# Battery_Module_Dev_Contacts.net
KiCad netlist of a schematic drawn in Altium Designer
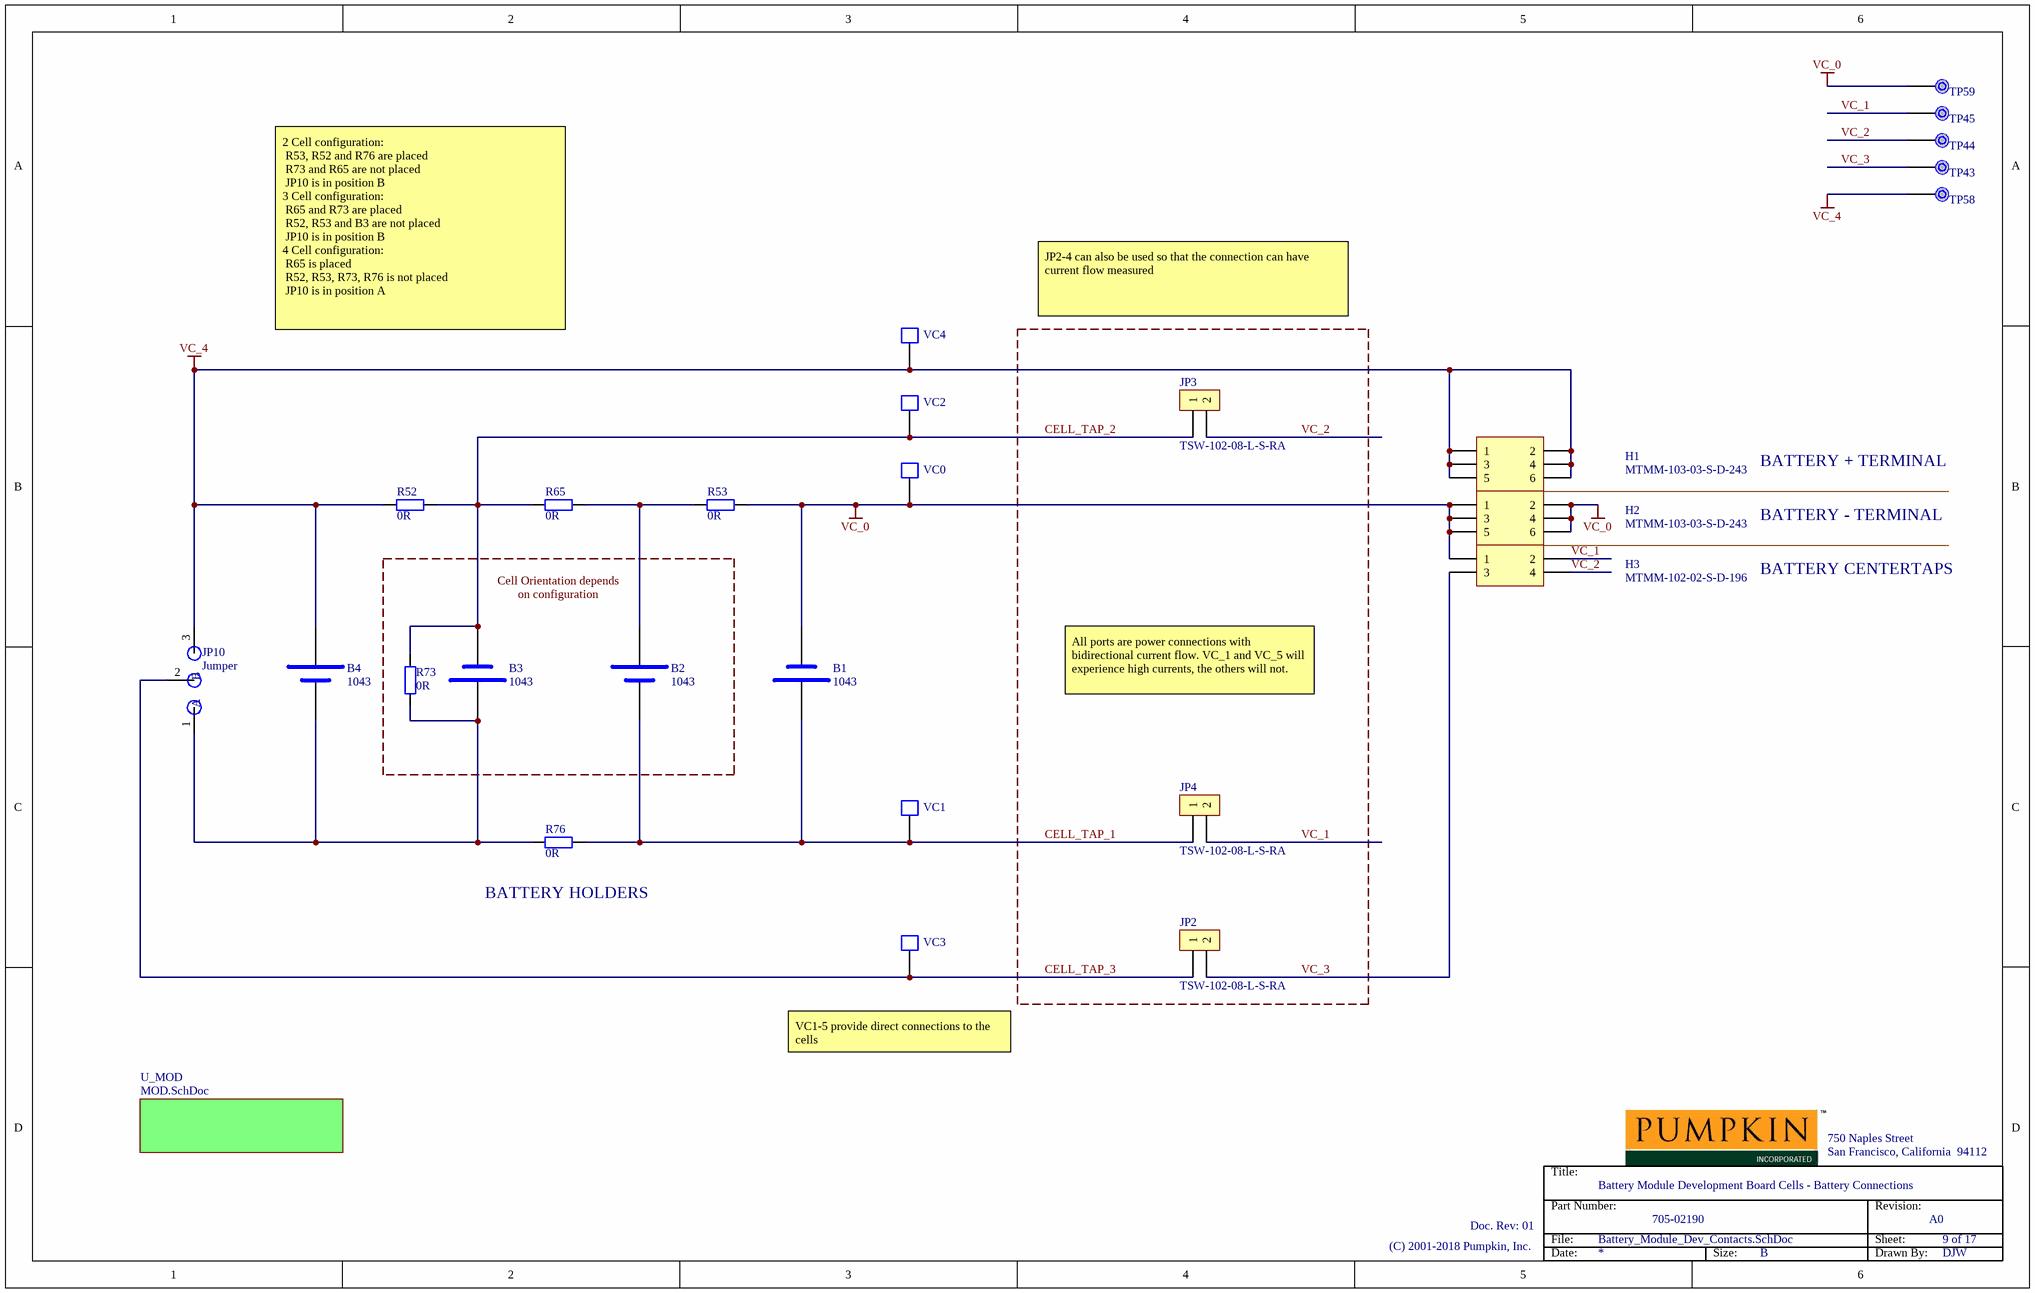
[diagram p0: Battery_Module_Dev_Contacts.SchDoc]

(export (version "E")
  (design (tool "Eeschema 10.0.6"))
  (components
    (comp (ref "B1")
      (value "1043")
      (footprint "1043")
      (description "Battery 18650 Holder")
      (libsource (lib "Supernova Connectors") (part "1043"))
    )
    (comp (ref "B2")
      (value "1043")
      (footprint "1043 - non-polar")
      (description "Battery 18650 Holder")
      (libsource (lib "Supernova Connectors") (part "1043"))
    )
    (comp (ref "B3")
      (value "1043")
      (footprint "1043 - non-polar")
      (description "Battery 18650 Holder")
      (libsource (lib "Supernova Connectors") (part "1043"))
    )
    (comp (ref "B4")
      (value "1043")
      (footprint "1043")
      (description "Battery 18650 Holder")
      (libsource (lib "Supernova Connectors") (part "1043"))
    )
    (comp (ref "H1")
      (value "MTMM-103-03-S-D-243")
      (footprint "MTMM-103-03-S-D-243")
      (description "Header 3x2 TH thru-board 2mm")
      (libsource (lib "Supernova Connectors") (part "MTMM-103-03-S-D-243"))
    )
    (comp (ref "H2")
      (value "MTMM-103-03-S-D-243")
      (footprint "MTMM-103-03-S-D-243")
      (description "Header 3x2 TH thru-board 2mm")
      (libsource (lib "Supernova Connectors") (part "MTMM-103-03-S-D-243"))
    )
    (comp (ref "H3")
      (value "MTMM-102-02-S-D-196")
      (footprint "MTMM-102-02-S-D-196")
      (description "Header 2x2 TH thru-board 2mm")
      (libsource (lib "Supernova Connectors") (part "MTMM-102-02-S-D-196"))
    )
    (comp (ref "JP2")
      (value "TSW-102-08-L-S-RA")
      (footprint "HDR1X2HTH")
      (description "Header 2x1 RA TH")
      (libsource (lib "Supernova Connectors") (part "TSW-102-08-L-S-RA"))
    )
    (comp (ref "JP3")
      (value "TSW-102-08-L-S-RA")
      (footprint "HDR1X2HTH")
      (description "Header 2x1 RA TH")
      (libsource (lib "Supernova Connectors") (part "TSW-102-08-L-S-RA"))
    )
    (comp (ref "JP4")
      (value "TSW-102-08-L-S-RA")
      (footprint "HDR1X2HTH")
      (description "Header 2x1 RA TH")
      (libsource (lib "Supernova Connectors") (part "TSW-102-08-L-S-RA"))
    )
    (comp (ref "JP10")
      (value "Jumper")
      (footprint "0805 RES 2 way jumper")
      (description "Jumper 0805 2 pos")
      (libsource (lib "Supernova Resistors") (part "Jumper 2 way 0805"))
    )
    (comp (ref "R52")
      (value "0R")
      (footprint "2512 RES")
      (description "Resistor 0R 2512 1W")
      (libsource (lib "") (part "Resistor 0R 2512_2"))
    )
    (comp (ref "R53")
      (value "0R")
      (footprint "2512 RES")
      (description "Resistor 0R 2512 1W")
      (libsource (lib "") (part "Resistor 0R 2512_1"))
    )
    (comp (ref "R65")
      (value "0R")
      (footprint "2512 RES")
      (description "Resistor 0R 2512 1W")
      (libsource (lib "") (part "Resistor 0R 2512_1"))
    )
    (comp (ref "R73")
      (value "0R")
      (footprint "2512 RES")
      (description "Resistor 0R 2512 1W")
      (libsource (lib "Supernova Resistors") (part "Resistor 0R 2512"))
    )
    (comp (ref "R76")
      (value "0R")
      (footprint "2512 RES")
      (description "Resistor 0R 2512 1W")
      (libsource (lib "") (part "Resistor 0R 2512_1"))
    )
    (comp (ref "TP43")
      (value "Testpoint")
      (footprint "Testpoint")
      (libsource (lib "Supernova Connectors") (part "Testpoint"))
    )
    (comp (ref "TP44")
      (value "Testpoint")
      (footprint "Testpoint")
      (libsource (lib "Supernova Connectors") (part "Testpoint"))
    )
    (comp (ref "TP45")
      (value "Testpoint")
      (footprint "Testpoint")
      (libsource (lib "Supernova Connectors") (part "Testpoint"))
    )
    (comp (ref "TP58")
      (value "Testpoint")
      (footprint "Testpoint")
      (libsource (lib "Supernova Connectors") (part "Testpoint"))
    )
    (comp (ref "TP59")
      (value "Testpoint")
      (footprint "Testpoint")
      (libsource (lib "Supernova Connectors") (part "Testpoint"))
    )
    (comp (ref "VC0")
      (value "Hook")
      (footprint "Hook")
      (description "Testpoint Hook")
      (fields
        (field (name "MANUFACTURER") "Keystone Electronics")
        (field (name "MANUFACTURER PART NUMBER") "5016")
      )
      (libsource (lib "Supernova Connectors") (part "Hook"))
    )
    (comp (ref "VC1")
      (value "Hook")
      (footprint "Hook")
      (description "Testpoint Hook")
      (fields
        (field (name "MANUFACTURER") "Keystone Electronics")
        (field (name "MANUFACTURER PART NUMBER") "5016")
      )
      (libsource (lib "Supernova Connectors") (part "Hook"))
    )
    (comp (ref "VC2")
      (value "Hook")
      (footprint "Hook")
      (description "Testpoint Hook")
      (fields
        (field (name "MANUFACTURER") "Keystone Electronics")
        (field (name "MANUFACTURER PART NUMBER") "5016")
      )
      (libsource (lib "Supernova Connectors") (part "Hook"))
    )
    (comp (ref "VC3")
      (value "Hook")
      (footprint "Hook")
      (description "Testpoint Hook")
      (fields
        (field (name "MANUFACTURER") "Keystone Electronics")
        (field (name "MANUFACTURER PART NUMBER") "5016")
      )
      (libsource (lib "Supernova Connectors") (part "Hook"))
    )
    (comp (ref "VC4")
      (value "Hook")
      (footprint "Hook")
      (description "Testpoint Hook")
      (fields
        (field (name "MANUFACTURER") "Keystone Electronics")
        (field (name "MANUFACTURER PART NUMBER") "5016")
      )
      (libsource (lib "Supernova Connectors") (part "Hook"))
    )
  )
  (nets
    (net (code "1") (name "/CELL_TAP_1") (class "Default")
      (node (ref "B1") (pin "1") (pinfunction "1_1") (pintype "passive"))
      (node (ref "B2") (pin "2") (pinfunction "2_2") (pintype "passive"))
      (node (ref "JP4") (pin "1") (pinfunction "1_1") (pintype "passive"))
      (node (ref "R76") (pin "1") (pinfunction "1_1") (pintype "passive"))
      (node (ref "VC1") (pin "1") (pinfunction "Hook_1") (pintype "passive"))
    )
    (net (code "2") (name "/CELL_TAP_2") (class "Default")
      (node (ref "B3") (pin "2") (pinfunction "2_2") (pintype "passive"))
      (node (ref "JP3") (pin "1") (pinfunction "1_1") (pintype "passive"))
      (node (ref "R52") (pin "2") (pinfunction "2_2") (pintype "passive"))
      (node (ref "R65") (pin "2") (pinfunction "2_2") (pintype "passive"))
      (node (ref "R73") (pin "2") (pinfunction "2_2") (pintype "passive"))
      (node (ref "VC2") (pin "1") (pinfunction "Hook_1") (pintype "passive"))
    )
    (net (code "3") (name "/CELL_TAP_3") (class "Default")
      (node (ref "JP10") (pin "2") (pinfunction "5_2") (pintype "passive"))
      (node (ref "JP2") (pin "1") (pinfunction "1_1") (pintype "passive"))
      (node (ref "VC3") (pin "1") (pinfunction "Hook_1") (pintype "passive"))
    )
    (net (code "4") (name "/VC_1") (class "Default")
      (node (ref "H3") (pin "2") (pinfunction "2_2") (pintype "passive"))
      (node (ref "JP4") (pin "2") (pinfunction "2_2") (pintype "passive"))
      (node (ref "TP45") (pin "1") (pinfunction "1_1") (pintype "passive"))
    )
    (net (code "5") (name "/VC_2") (class "Default")
      (node (ref "H3") (pin "4") (pinfunction "4_4") (pintype "passive"))
      (node (ref "JP3") (pin "2") (pinfunction "2_2") (pintype "passive"))
      (node (ref "TP44") (pin "1") (pinfunction "1_1") (pintype "passive"))
    )
    (net (code "6") (name "/VC_3") (class "Default")
      (node (ref "H3") (pin "3") (pinfunction "3_3") (pintype "passive"))
      (node (ref "JP2") (pin "2") (pinfunction "2_2") (pintype "passive"))
      (node (ref "TP43") (pin "1") (pinfunction "1_1") (pintype "passive"))
    )
    (net (code "7") (name "Net-(B2-Pad1)") (class "Default")
      (node (ref "B2") (pin "1") (pinfunction "1_1") (pintype "passive"))
      (node (ref "R53") (pin "2") (pinfunction "2_2") (pintype "passive"))
      (node (ref "R65") (pin "1") (pinfunction "1_1") (pintype "passive"))
    )
    (net (code "8") (name "Net-(B3-Pad1)") (class "Default")
      (node (ref "B3") (pin "1") (pinfunction "1_1") (pintype "passive"))
      (node (ref "B4") (pin "2") (pinfunction "2_2") (pintype "passive"))
      (node (ref "JP10") (pin "1") (pinfunction "5_1") (pintype "passive"))
      (node (ref "R73") (pin "1") (pinfunction "1_1") (pintype "passive"))
      (node (ref "R76") (pin "2") (pinfunction "2_2") (pintype "passive"))
    )
    (net (code "9") (name "VC_0") (class "Default")
      (node (ref "B1") (pin "2") (pinfunction "2_2") (pintype "passive"))
      (node (ref "H2") (pin "1") (pinfunction "1_1") (pintype "passive"))
      (node (ref "H2") (pin "2") (pinfunction "2_2") (pintype "passive"))
      (node (ref "H2") (pin "3") (pinfunction "3_3") (pintype "passive"))
      (node (ref "H2") (pin "4") (pinfunction "4_4") (pintype "passive"))
      (node (ref "H2") (pin "5") (pinfunction "5_5") (pintype "passive"))
      (node (ref "H2") (pin "6") (pinfunction "6_6") (pintype "passive"))
      (node (ref "H3") (pin "1") (pinfunction "1_1") (pintype "passive"))
      (node (ref "R53") (pin "1") (pinfunction "1_1") (pintype "passive"))
      (node (ref "TP59") (pin "1") (pinfunction "1_1") (pintype "passive"))
      (node (ref "VC0") (pin "1") (pinfunction "Hook_1") (pintype "passive"))
    )
    (net (code "10") (name "VC_4") (class "Default")
      (node (ref "B4") (pin "1") (pinfunction "1_1") (pintype "passive"))
      (node (ref "H1") (pin "1") (pinfunction "1_1") (pintype "passive"))
      (node (ref "H1") (pin "2") (pinfunction "2_2") (pintype "passive"))
      (node (ref "H1") (pin "3") (pinfunction "3_3") (pintype "passive"))
      (node (ref "H1") (pin "4") (pinfunction "4_4") (pintype "passive"))
      (node (ref "H1") (pin "5") (pinfunction "5_5") (pintype "passive"))
      (node (ref "H1") (pin "6") (pinfunction "6_6") (pintype "passive"))
      (node (ref "JP10") (pin "3") (pinfunction "5_3") (pintype "passive"))
      (node (ref "R52") (pin "1") (pinfunction "1_1") (pintype "passive"))
      (node (ref "TP58") (pin "1") (pinfunction "1_1") (pintype "passive"))
      (node (ref "VC4") (pin "1") (pinfunction "Hook_1") (pintype "passive"))
    )
  )
)
